# power.net
KiCad netlist of a schematic drawn in Altium Designer
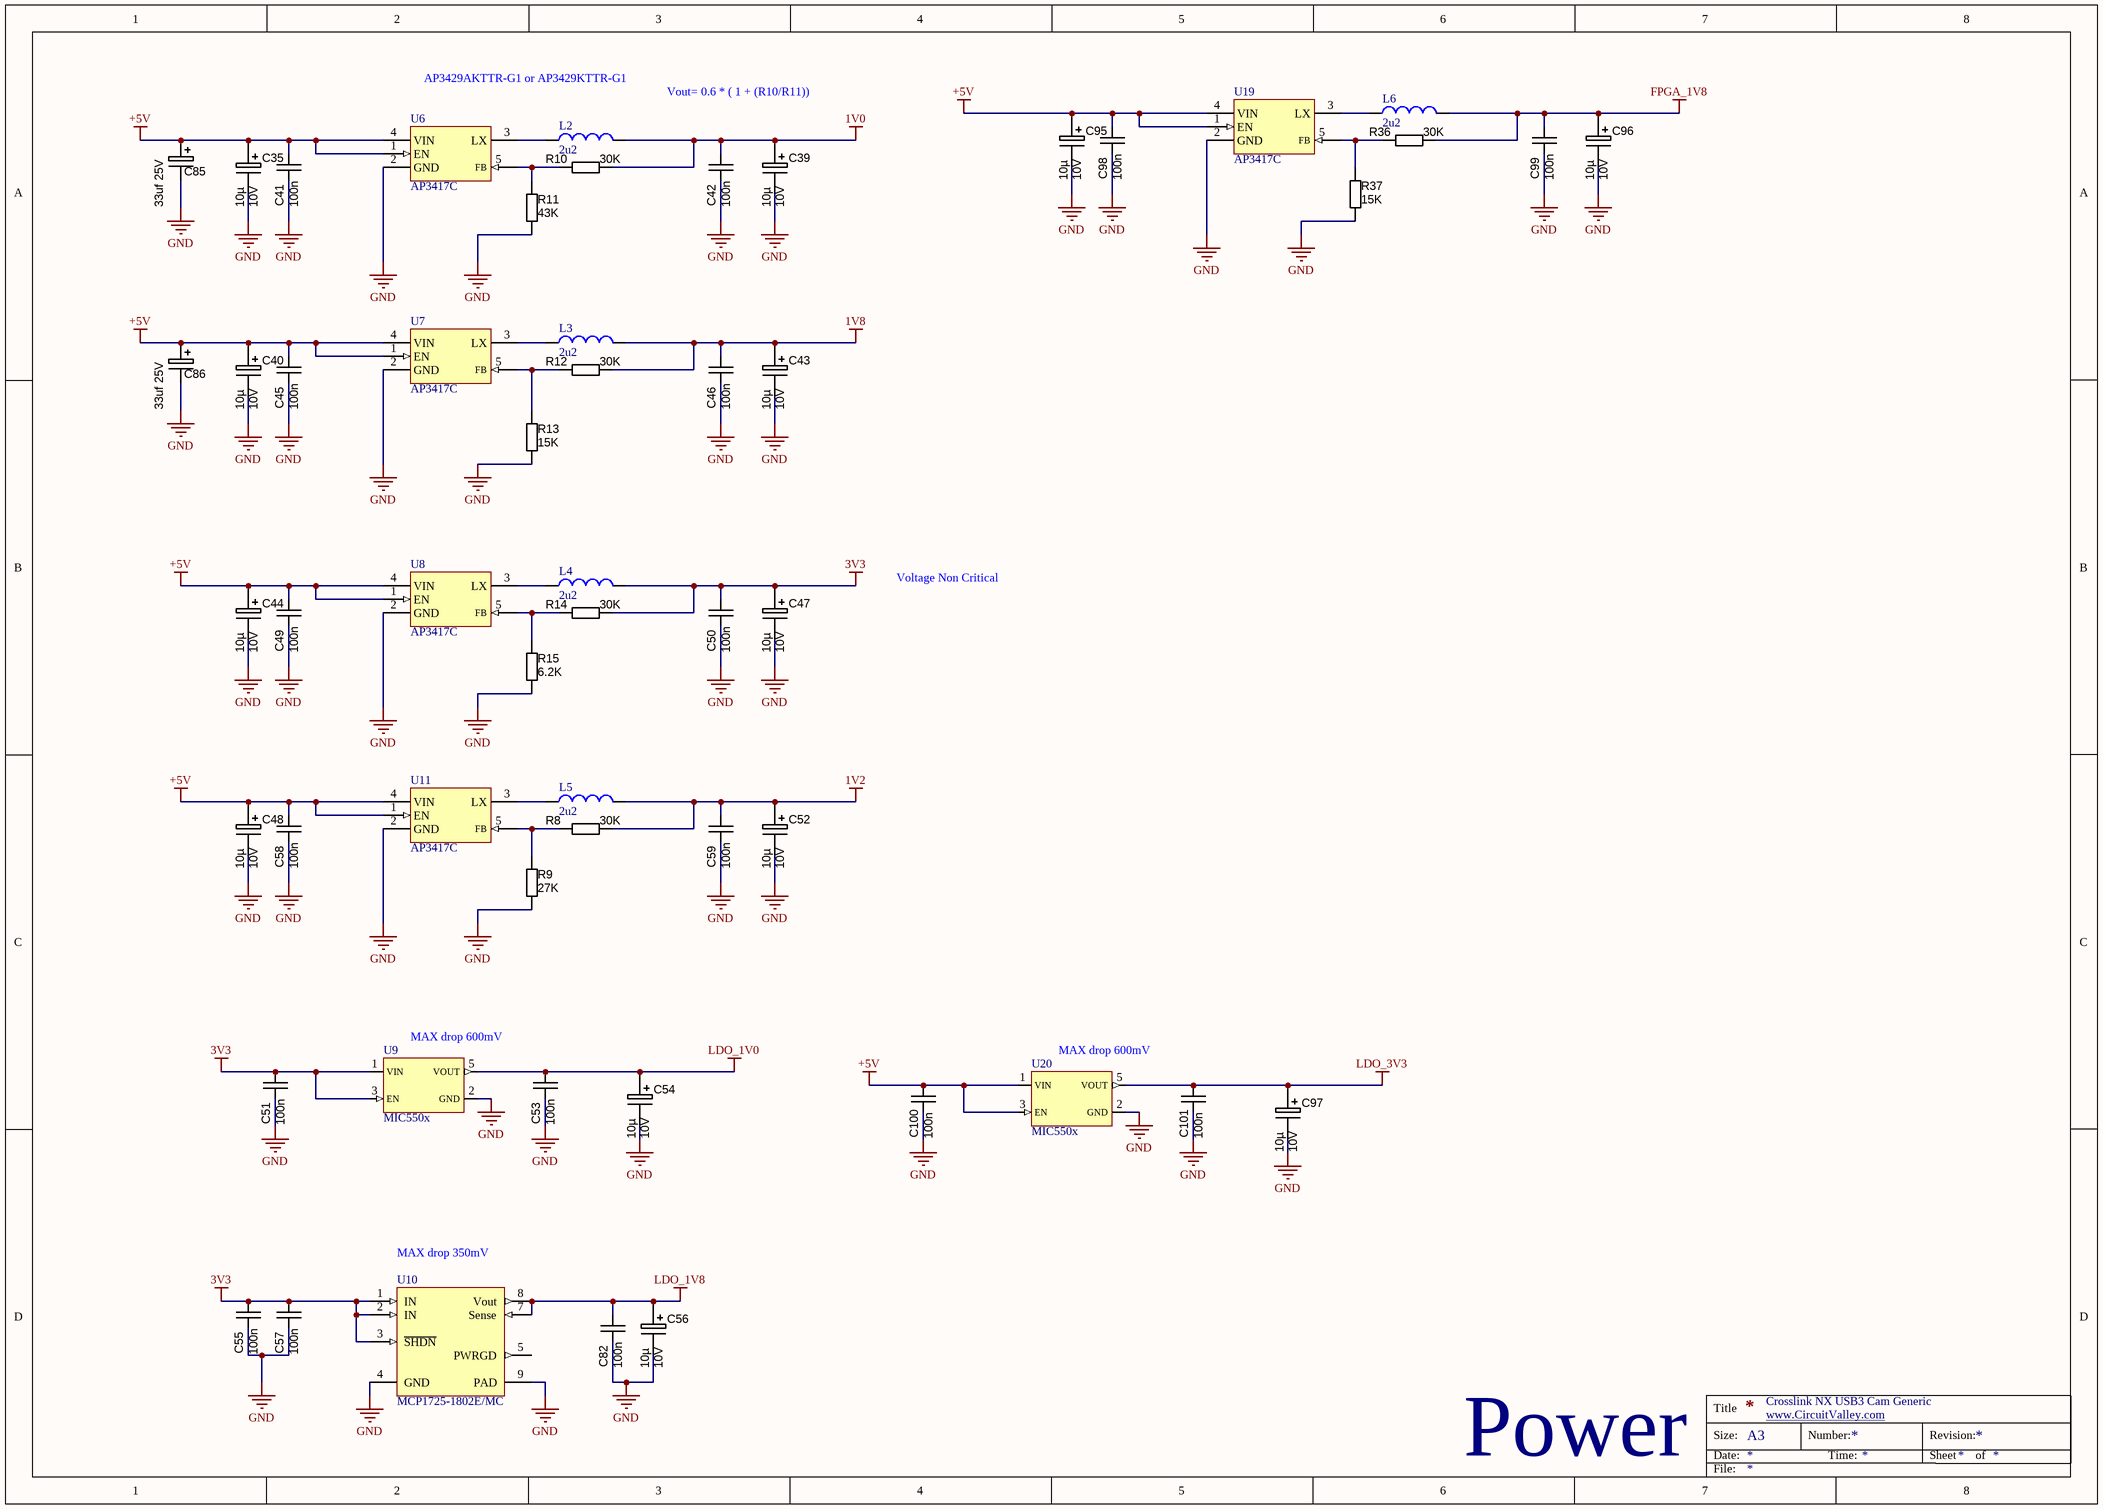
[diagram p0: power.SchDoc]

(export (version "E")
  (design (tool "Eeschema 10.0.6"))
  (components
    (comp (ref "C35")
      (value "10µ")
      (footprint "CAPMP3528X210N")
      (description "Capacitor SMD Tantalum 47uF 20% 6.3V 1210")
      (fields (field (name "TOLERANCE") "±20%") (field (name "RATINGS") "10V"))
      (libsource (lib "PBL - Capacitors") (part "CAPT_47u_1210_6V3"))
    )
    (comp (ref "C39")
      (value "10µ")
      (footprint "CAPMP3528X210N")
      (description "Capacitor SMD Tantalum 47uF 20% 6.3V 1210")
      (fields (field (name "TOLERANCE") "±20%") (field (name "RATINGS") "10V"))
      (libsource (lib "PBL - Capacitors") (part "CAPT_47u_1210_6V3"))
    )
    (comp (ref "C40")
      (value "10µ")
      (footprint "CAPMP3528X210N")
      (description "Capacitor SMD Tantalum 47uF 20% 6.3V 1210")
      (fields (field (name "TOLERANCE") "±20%") (field (name "RATINGS") "10V"))
      (libsource (lib "PBL - Capacitors") (part "CAPT_47u_1210_6V3"))
    )
    (comp (ref "C41")
      (value "100n")
      (footprint "CAPC1608N")
      (description "Capacitor SMD Cer 10pF 5% 50V NP0 0603")
      (fields (field (name "TOLERANCE") "±5%") (field (name "PART") "C0603X104K5RAC"))
      (libsource (lib "PBL - Capacitors") (part "CAPC_10p_0603_NP0_1%_50V"))
    )
    (comp (ref "C42")
      (value "100n")
      (footprint "CAPC1608N")
      (description "Capacitor SMD Cer 10pF 5% 50V NP0 0603")
      (fields (field (name "TOLERANCE") "±5%") (field (name "PART") "C0603X104K5RAC"))
      (libsource (lib "PBL - Capacitors") (part "CAPC_10p_0603_NP0_1%_50V"))
    )
    (comp (ref "C43")
      (value "10µ")
      (footprint "CAPMP3528X210N")
      (description "Capacitor SMD Tantalum 47uF 20% 6.3V 1210")
      (fields (field (name "TOLERANCE") "±20%") (field (name "RATINGS") "10V"))
      (libsource (lib "PBL - Capacitors") (part "CAPT_47u_1210_6V3"))
    )
    (comp (ref "C44")
      (value "10µ")
      (footprint "CAPMP3528X210N")
      (description "Capacitor SMD Tantalum 47uF 20% 6.3V 1210")
      (fields (field (name "TOLERANCE") "±20%") (field (name "RATINGS") "10V"))
      (libsource (lib "PBL - Capacitors") (part "CAPT_47u_1210_6V3"))
    )
    (comp (ref "C45")
      (value "100n")
      (footprint "CAPC1608N")
      (description "Capacitor SMD Cer 10pF 5% 50V NP0 0603")
      (fields (field (name "TOLERANCE") "±5%") (field (name "PART") "C0603X104K5RAC"))
      (libsource (lib "PBL - Capacitors") (part "CAPC_10p_0603_NP0_1%_50V"))
    )
    (comp (ref "C46")
      (value "100n")
      (footprint "CAPC1608N")
      (description "Capacitor SMD Cer 10pF 5% 50V NP0 0603")
      (fields (field (name "TOLERANCE") "±5%") (field (name "PART") "C0603X104K5RAC"))
      (libsource (lib "PBL - Capacitors") (part "CAPC_10p_0603_NP0_1%_50V"))
    )
    (comp (ref "C47")
      (value "10µ")
      (footprint "CAPMP3528X210N")
      (description "Capacitor SMD Tantalum 47uF 20% 6.3V 1210")
      (fields (field (name "TOLERANCE") "±20%") (field (name "RATINGS") "10V"))
      (libsource (lib "PBL - Capacitors") (part "CAPT_47u_1210_6V3"))
    )
    (comp (ref "C48")
      (value "10µ")
      (footprint "CAPMP3528X210N")
      (description "Capacitor SMD Tantalum 47uF 20% 6.3V 1210")
      (fields (field (name "TOLERANCE") "±20%") (field (name "RATINGS") "10V"))
      (libsource (lib "PBL - Capacitors") (part "CAPT_47u_1210_6V3"))
    )
    (comp (ref "C49")
      (value "100n")
      (footprint "CAPC1608N")
      (description "Capacitor SMD Cer 10pF 5% 50V NP0 0603")
      (fields (field (name "TOLERANCE") "±5%") (field (name "PART") "C0603X104K5RAC"))
      (libsource (lib "PBL - Capacitors") (part "CAPC_10p_0603_NP0_1%_50V"))
    )
    (comp (ref "C50")
      (value "100n")
      (footprint "CAPC1608N")
      (description "Capacitor SMD Cer 10pF 5% 50V NP0 0603")
      (fields (field (name "TOLERANCE") "±5%") (field (name "PART") "C0603X104K5RAC"))
      (libsource (lib "PBL - Capacitors") (part "CAPC_10p_0603_NP0_1%_50V"))
    )
    (comp (ref "C51")
      (value "100n")
      (footprint "CAPC1608N")
      (description "Capacitor SMD Cer 10pF 5% 50V NP0 0603")
      (fields (field (name "TOLERANCE") "±5%") (field (name "PART") "C0603X104K5RAC"))
      (libsource (lib "PBL - Capacitors") (part "CAPC_10p_0603_NP0_1%_50V"))
    )
    (comp (ref "C52")
      (value "10µ")
      (footprint "CAPMP3528X210N")
      (description "Capacitor SMD Tantalum 47uF 20% 6.3V 1210")
      (fields (field (name "TOLERANCE") "±20%") (field (name "RATINGS") "10V"))
      (libsource (lib "PBL - Capacitors") (part "CAPT_47u_1210_6V3"))
    )
    (comp (ref "C53")
      (value "100n")
      (footprint "CAPC1608N")
      (description "Capacitor SMD Cer 10pF 5% 50V NP0 0603")
      (fields (field (name "TOLERANCE") "±5%") (field (name "PART") "C0603X104K5RAC"))
      (libsource (lib "PBL - Capacitors") (part "CAPC_10p_0603_NP0_1%_50V"))
    )
    (comp (ref "C54")
      (value "10µ")
      (footprint "CAPMP3528X210N")
      (description "Capacitor SMD Tantalum 47uF 20% 6.3V 1210")
      (fields (field (name "TOLERANCE") "±20%") (field (name "RATINGS") "10V"))
      (libsource (lib "PBL - Capacitors") (part "CAPT_47u_1210_6V3"))
    )
    (comp (ref "C55")
      (value "100n")
      (footprint "CAPC1608N")
      (description "Capacitor SMD Cer 10pF 5% 50V NP0 0603")
      (fields (field (name "TOLERANCE") "±5%") (field (name "PART") "C0603X104K5RAC"))
      (libsource (lib "PBL - Capacitors") (part "CAPC_10p_0603_NP0_1%_50V"))
    )
    (comp (ref "C56")
      (value "10µ")
      (footprint "CAPMP3528X210N")
      (description "Capacitor SMD Tantalum 47uF 20% 6.3V 1210")
      (fields (field (name "TOLERANCE") "±20%") (field (name "RATINGS") "10V"))
      (libsource (lib "PBL - Capacitors") (part "CAPT_47u_1210_6V3"))
    )
    (comp (ref "C57")
      (value "100n")
      (footprint "CAPC1608N")
      (description "Capacitor SMD Cer 10pF 5% 50V NP0 0603")
      (fields (field (name "TOLERANCE") "±5%") (field (name "PART") "C0603X104K5RAC"))
      (libsource (lib "PBL - Capacitors") (part "CAPC_10p_0603_NP0_1%_50V"))
    )
    (comp (ref "C58")
      (value "100n")
      (footprint "CAPC1608N")
      (description "Capacitor SMD Cer 10pF 5% 50V NP0 0603")
      (fields (field (name "TOLERANCE") "±5%") (field (name "PART") "C0603X104K5RAC"))
      (libsource (lib "PBL - Capacitors") (part "CAPC_10p_0603_NP0_1%_50V"))
    )
    (comp (ref "C59")
      (value "100n")
      (footprint "CAPC1608N")
      (description "Capacitor SMD Cer 10pF 5% 50V NP0 0603")
      (fields (field (name "TOLERANCE") "±5%") (field (name "PART") "C0603X104K5RAC"))
      (libsource (lib "PBL - Capacitors") (part "CAPC_10p_0603_NP0_1%_50V"))
    )
    (comp (ref "C82")
      (value "100n")
      (footprint "CAPC1608N")
      (description "Capacitor SMD Cer 10pF 5% 50V NP0 0603")
      (fields (field (name "TOLERANCE") "±5%") (field (name "PART") "C0603X104K5RAC"))
      (libsource (lib "PBL - Capacitors") (part "CAPC_10p_0603_NP0_1%_50V"))
    )
    (comp (ref "C85")
      (value "33uf 25V")
      (footprint "CAPMP7343X310N")
      (description "Capacitor SMD Tant 330uF 20% 6V3 2917")
      (fields
        (field (name "TOLERANCE") "±20%")
        (field (name "MANUFACTURER PART NUMBER") "T520D337M006ATE015")
      )
      (libsource (lib "PBL - Capacitors") (part "CAPT_330u_2917_6V3"))
    )
    (comp (ref "C86")
      (value "33uf 25V")
      (footprint "CAPMP7343X310N")
      (description "Capacitor SMD Tant 330uF 20% 6V3 2917")
      (fields
        (field (name "TOLERANCE") "±20%")
        (field (name "MANUFACTURER PART NUMBER") "T520D337M006ATE015")
      )
      (libsource (lib "PBL - Capacitors") (part "CAPT_330u_2917_6V3"))
    )
    (comp (ref "C95")
      (value "10µ")
      (footprint "CAPMP3528X210N")
      (description "Capacitor SMD Tantalum 47uF 20% 6.3V 1210")
      (fields (field (name "TOLERANCE") "±20%") (field (name "RATINGS") "10V"))
      (libsource (lib "PBL - Capacitors") (part "CAPT_47u_1210_6V3"))
    )
    (comp (ref "C96")
      (value "10µ")
      (footprint "CAPMP3528X210N")
      (description "Capacitor SMD Tantalum 47uF 20% 6.3V 1210")
      (fields (field (name "TOLERANCE") "±20%") (field (name "RATINGS") "10V"))
      (libsource (lib "PBL - Capacitors") (part "CAPT_47u_1210_6V3"))
    )
    (comp (ref "C97")
      (value "10µ")
      (footprint "CAPMP3528X210N")
      (description "Capacitor SMD Tantalum 47uF 20% 6.3V 1210")
      (fields (field (name "TOLERANCE") "±20%") (field (name "RATINGS") "10V"))
      (libsource (lib "PBL - Capacitors") (part "CAPT_47u_1210_6V3"))
    )
    (comp (ref "C98")
      (value "100n")
      (footprint "CAPC1608N")
      (description "Capacitor SMD Cer 10pF 5% 50V NP0 0603")
      (fields (field (name "TOLERANCE") "±5%") (field (name "PART") "C0603X104K5RAC"))
      (libsource (lib "PBL - Capacitors") (part "CAPC_10p_0603_NP0_1%_50V"))
    )
    (comp (ref "C99")
      (value "100n")
      (footprint "CAPC1608N")
      (description "Capacitor SMD Cer 10pF 5% 50V NP0 0603")
      (fields (field (name "TOLERANCE") "±5%") (field (name "PART") "C0603X104K5RAC"))
      (libsource (lib "PBL - Capacitors") (part "CAPC_10p_0603_NP0_1%_50V"))
    )
    (comp (ref "C100")
      (value "100n")
      (footprint "CAPC1608N")
      (description "Capacitor SMD Cer 10pF 5% 50V NP0 0603")
      (fields (field (name "TOLERANCE") "±5%") (field (name "PART") "C0603X104K5RAC"))
      (libsource (lib "PBL - Capacitors") (part "CAPC_10p_0603_NP0_1%_50V"))
    )
    (comp (ref "C101")
      (value "100n")
      (footprint "CAPC1608N")
      (description "Capacitor SMD Cer 10pF 5% 50V NP0 0603")
      (fields (field (name "TOLERANCE") "±5%") (field (name "PART") "C0603X104K5RAC"))
      (libsource (lib "PBL - Capacitors") (part "CAPC_10p_0603_NP0_1%_50V"))
    )
    (comp (ref "L2")
      (value "2u2")
      (footprint "TAIYO_NRS4018T2R2MDGJ")
      (fields (field (name "PARTNUMBER") "NRS4018T2R2MDGJ"))
      (libsource (lib "Inductor") (part "inductor_smd"))
    )
    (comp (ref "L3")
      (value "2u2")
      (footprint "TAIYO_NRS4018T2R2MDGJ")
      (fields (field (name "PARTNUMBER") "NRS4018T2R2MDGJ"))
      (libsource (lib "Inductor") (part "inductor_smd"))
    )
    (comp (ref "L4")
      (value "2u2")
      (footprint "TAIYO_NRS4018T2R2MDGJ")
      (fields (field (name "PARTNUMBER") "NRS4018T2R2MDGJ"))
      (libsource (lib "Inductor") (part "inductor_smd"))
    )
    (comp (ref "L5")
      (value "2u2")
      (footprint "TAIYO_NRS4018T2R2MDGJ")
      (fields (field (name "PARTNUMBER") "NRS4018T2R2MDGJ"))
      (libsource (lib "Inductor") (part "inductor_smd"))
    )
    (comp (ref "L6")
      (value "2u2")
      (footprint "TAIYO_NRS4018T2R2MDGJ")
      (fields (field (name "PARTNUMBER") "NRS4018T2R2MDGJ"))
      (libsource (lib "Inductor") (part "inductor_smd"))
    )
    (comp (ref "R8")
      (value "30K")
      (footprint "RESC1608N_ZERO")
      (description "Resistor SMD chip 0.0 Ohm 0.1W 0603")
      (fields (field (name "TOLERANCE") "±5%") (field (name "Comment") "Thick Film"))
      (libsource (lib "PBL - Resistors") (part "RES_0R_0603"))
    )
    (comp (ref "R9")
      (value "27K")
      (footprint "RESC1608N_ZERO")
      (description "Resistor SMD chip 0.0 Ohm 0.1W 0603")
      (fields (field (name "TOLERANCE") "±5%") (field (name "Comment") "Thick Film"))
      (libsource (lib "") (part "RES_0R_0603_1"))
    )
    (comp (ref "R10")
      (value "30K")
      (footprint "RESC1608N_ZERO")
      (description "Resistor SMD chip 0.0 Ohm 0.1W 0603")
      (fields (field (name "TOLERANCE") "±5%") (field (name "Comment") "Thick Film"))
      (libsource (lib "PBL - Resistors") (part "RES_0R_0603"))
    )
    (comp (ref "R11")
      (value "43K")
      (footprint "RESC1608N_ZERO")
      (description "Resistor SMD chip 0.0 Ohm 0.1W 0603")
      (fields (field (name "TOLERANCE") "±5%") (field (name "Comment") "Thick Film"))
      (libsource (lib "") (part "RES_0R_0603_1"))
    )
    (comp (ref "R12")
      (value "30K")
      (footprint "RESC1608N_ZERO")
      (description "Resistor SMD chip 0.0 Ohm 0.1W 0603")
      (fields (field (name "TOLERANCE") "±5%") (field (name "Comment") "Thick Film"))
      (libsource (lib "PBL - Resistors") (part "RES_0R_0603"))
    )
    (comp (ref "R13")
      (value "15K")
      (footprint "RESC1608N_ZERO")
      (description "Resistor SMD chip 0.0 Ohm 0.1W 0603")
      (fields (field (name "TOLERANCE") "±5%") (field (name "Comment") "Thick Film"))
      (libsource (lib "") (part "RES_0R_0603_1"))
    )
    (comp (ref "R14")
      (value "30K")
      (footprint "RESC1608N_ZERO")
      (description "Resistor SMD chip 0.0 Ohm 0.1W 0603")
      (fields (field (name "TOLERANCE") "±5%") (field (name "Comment") "Thick Film"))
      (libsource (lib "PBL - Resistors") (part "RES_0R_0603"))
    )
    (comp (ref "R15")
      (value "6.2K")
      (footprint "RESC1608N_ZERO")
      (description "Resistor SMD chip 0.0 Ohm 0.1W 0603")
      (fields (field (name "TOLERANCE") "±5%") (field (name "Comment") "Thick Film"))
      (libsource (lib "") (part "RES_0R_0603_1"))
    )
    (comp (ref "R36")
      (value "30K")
      (footprint "RESC1608N_ZERO")
      (description "Resistor SMD chip 0.0 Ohm 0.1W 0603")
      (fields (field (name "TOLERANCE") "±5%") (field (name "Comment") "Thick Film"))
      (libsource (lib "PBL - Resistors") (part "RES_0R_0603"))
    )
    (comp (ref "R37")
      (value "15K")
      (footprint "RESC1608N_ZERO")
      (description "Resistor SMD chip 0.0 Ohm 0.1W 0603")
      (fields (field (name "TOLERANCE") "±5%") (field (name "Comment") "Thick Film"))
      (libsource (lib "") (part "RES_0R_0603_1"))
    )
    (comp (ref "U6") (value "AP3417C") (footprint "SOT23-5") (libsource (lib "cvlib") (part "AP3417C")))
    (comp (ref "U7") (value "AP3417C") (footprint "SOT23-5") (libsource (lib "cvlib") (part "AP3417C")))
    (comp (ref "U8") (value "AP3417C") (footprint "SOT23-5") (libsource (lib "cvlib") (part "AP3417C")))
    (comp (ref "U9") (value "MIC550x") (footprint "SOT23-5") (libsource (lib "cvlib") (part "MIC550x")))
    (comp (ref "U10")
      (value "MCP1725-1802E/MC")
      (footprint "DFN8_3x2")
      (description "LDO")
      (libsource (lib "cvlib") (part "MCP1725"))
    )
    (comp (ref "U11") (value "AP3417C") (footprint "SOT23-5") (libsource (lib "cvlib") (part "AP3417C")))
    (comp (ref "U19") (value "AP3417C") (footprint "SOT23-5") (libsource (lib "cvlib") (part "AP3417C")))
    (comp (ref "U20") (value "MIC550x") (footprint "SOT23-5") (libsource (lib "cvlib") (part "MIC550x")))
  )
  (nets
    (net (code "1") (name "+5V") (class "Default")
      (node (ref "C100") (pin "2") (pintype "passive"))
      (node (ref "C35") (pin "1") (pintype "passive"))
      (node (ref "C40") (pin "1") (pintype "passive"))
      (node (ref "C41") (pin "2") (pintype "passive"))
      (node (ref "C44") (pin "1") (pintype "passive"))
      (node (ref "C45") (pin "2") (pintype "passive"))
      (node (ref "C48") (pin "1") (pintype "passive"))
      (node (ref "C49") (pin "2") (pintype "passive"))
      (node (ref "C58") (pin "2") (pintype "passive"))
      (node (ref "C85") (pin "1") (pintype "passive"))
      (node (ref "C86") (pin "1") (pintype "passive"))
      (node (ref "C95") (pin "1") (pintype "passive"))
      (node (ref "C98") (pin "2") (pintype "passive"))
      (node (ref "U11") (pin "1") (pinfunction "EN_1") (pintype "input"))
      (node (ref "U11") (pin "4") (pinfunction "VIN_4") (pintype "power_in"))
      (node (ref "U19") (pin "1") (pinfunction "EN_1") (pintype "input"))
      (node (ref "U19") (pin "4") (pinfunction "VIN_4") (pintype "power_in"))
      (node (ref "U20") (pin "1") (pinfunction "VIN_1") (pintype "power_in"))
      (node (ref "U20") (pin "3") (pinfunction "EN_3") (pintype "input"))
      (node (ref "U6") (pin "1") (pinfunction "EN_1") (pintype "input"))
      (node (ref "U6") (pin "4") (pinfunction "VIN_4") (pintype "power_in"))
      (node (ref "U7") (pin "1") (pinfunction "EN_1") (pintype "input"))
      (node (ref "U7") (pin "4") (pinfunction "VIN_4") (pintype "power_in"))
      (node (ref "U8") (pin "1") (pinfunction "EN_1") (pintype "input"))
      (node (ref "U8") (pin "4") (pinfunction "VIN_4") (pintype "power_in"))
    )
    (net (code "2") (name "1V0") (class "Default")
      (node (ref "C39") (pin "1") (pintype "passive"))
      (node (ref "C42") (pin "2") (pintype "passive"))
      (node (ref "L2") (pin "2") (pinfunction "2_2") (pintype "passive"))
      (node (ref "R10") (pin "1") (pinfunction "1_1") (pintype "passive"))
    )
    (net (code "3") (name "1V2") (class "Default")
      (node (ref "C52") (pin "1") (pintype "passive"))
      (node (ref "C59") (pin "2") (pintype "passive"))
      (node (ref "L5") (pin "2") (pinfunction "2_2") (pintype "passive"))
      (node (ref "R8") (pin "1") (pinfunction "1_1") (pintype "passive"))
    )
    (net (code "4") (name "1V8") (class "Default")
      (node (ref "C43") (pin "1") (pintype "passive"))
      (node (ref "C46") (pin "2") (pintype "passive"))
      (node (ref "L3") (pin "2") (pinfunction "2_2") (pintype "passive"))
      (node (ref "R12") (pin "1") (pinfunction "1_1") (pintype "passive"))
    )
    (net (code "5") (name "3V3") (class "Default")
      (node (ref "C47") (pin "1") (pintype "passive"))
      (node (ref "C50") (pin "2") (pintype "passive"))
      (node (ref "C51") (pin "2") (pintype "passive"))
      (node (ref "C55") (pin "2") (pintype "passive"))
      (node (ref "C57") (pin "2") (pintype "passive"))
      (node (ref "L4") (pin "2") (pinfunction "2_2") (pintype "passive"))
      (node (ref "R14") (pin "1") (pinfunction "1_1") (pintype "passive"))
      (node (ref "U10") (pin "1") (pinfunction "IN_1") (pintype "input"))
      (node (ref "U10") (pin "2") (pinfunction "IN_2") (pintype "input"))
      (node (ref "U10") (pin "3") (pinfunction "~{SHDN}_3") (pintype "input"))
      (node (ref "U9") (pin "1") (pinfunction "VIN_1") (pintype "power_in"))
      (node (ref "U9") (pin "3") (pinfunction "EN_3") (pintype "input"))
    )
    (net (code "6") (name "FPGA_1V8") (class "Default")
      (node (ref "C96") (pin "1") (pintype "passive"))
      (node (ref "C99") (pin "2") (pintype "passive"))
      (node (ref "L6") (pin "2") (pinfunction "2_2") (pintype "passive"))
      (node (ref "R36") (pin "1") (pinfunction "1_1") (pintype "passive"))
    )
    (net (code "7") (name "GND") (class "Default")
      (node (ref "C100") (pin "1") (pintype "passive"))
      (node (ref "C101") (pin "1") (pintype "passive"))
      (node (ref "C35") (pin "2") (pintype "passive"))
      (node (ref "C39") (pin "2") (pintype "passive"))
      (node (ref "C40") (pin "2") (pintype "passive"))
      (node (ref "C41") (pin "1") (pintype "passive"))
      (node (ref "C42") (pin "1") (pintype "passive"))
      (node (ref "C43") (pin "2") (pintype "passive"))
      (node (ref "C44") (pin "2") (pintype "passive"))
      (node (ref "C45") (pin "1") (pintype "passive"))
      (node (ref "C46") (pin "1") (pintype "passive"))
      (node (ref "C47") (pin "2") (pintype "passive"))
      (node (ref "C48") (pin "2") (pintype "passive"))
      (node (ref "C49") (pin "1") (pintype "passive"))
      (node (ref "C50") (pin "1") (pintype "passive"))
      (node (ref "C51") (pin "1") (pintype "passive"))
      (node (ref "C52") (pin "2") (pintype "passive"))
      (node (ref "C53") (pin "1") (pintype "passive"))
      (node (ref "C54") (pin "2") (pintype "passive"))
      (node (ref "C55") (pin "1") (pintype "passive"))
      (node (ref "C56") (pin "2") (pintype "passive"))
      (node (ref "C57") (pin "1") (pintype "passive"))
      (node (ref "C58") (pin "1") (pintype "passive"))
      (node (ref "C59") (pin "1") (pintype "passive"))
      (node (ref "C82") (pin "1") (pintype "passive"))
      (node (ref "C85") (pin "2") (pintype "passive"))
      (node (ref "C86") (pin "2") (pintype "passive"))
      (node (ref "C95") (pin "2") (pintype "passive"))
      (node (ref "C96") (pin "2") (pintype "passive"))
      (node (ref "C97") (pin "2") (pintype "passive"))
      (node (ref "C98") (pin "1") (pintype "passive"))
      (node (ref "C99") (pin "1") (pintype "passive"))
      (node (ref "R11") (pin "2") (pinfunction "2_2") (pintype "passive"))
      (node (ref "R13") (pin "2") (pinfunction "2_2") (pintype "passive"))
      (node (ref "R15") (pin "2") (pinfunction "2_2") (pintype "passive"))
      (node (ref "R37") (pin "2") (pinfunction "2_2") (pintype "passive"))
      (node (ref "R9") (pin "2") (pinfunction "2_2") (pintype "passive"))
      (node (ref "U10") (pin "4") (pinfunction "GND_4") (pintype "passive"))
      (node (ref "U10") (pin "9") (pinfunction "PAD_9") (pintype "passive"))
      (node (ref "U11") (pin "2") (pinfunction "GND_2") (pintype "power_in"))
      (node (ref "U19") (pin "2") (pinfunction "GND_2") (pintype "power_in"))
      (node (ref "U20") (pin "2") (pinfunction "GND_2") (pintype "power_in"))
      (node (ref "U6") (pin "2") (pinfunction "GND_2") (pintype "power_in"))
      (node (ref "U7") (pin "2") (pinfunction "GND_2") (pintype "power_in"))
      (node (ref "U8") (pin "2") (pinfunction "GND_2") (pintype "power_in"))
      (node (ref "U9") (pin "2") (pinfunction "GND_2") (pintype "power_in"))
    )
    (net (code "8") (name "LDO_1V0") (class "Default")
      (node (ref "C53") (pin "2") (pintype "passive"))
      (node (ref "C54") (pin "1") (pintype "passive"))
      (node (ref "U9") (pin "5") (pinfunction "VOUT_5") (pintype "output"))
    )
    (net (code "9") (name "LDO_1V8") (class "Default")
      (node (ref "C56") (pin "1") (pintype "passive"))
      (node (ref "C82") (pin "2") (pintype "passive"))
      (node (ref "U10") (pin "7") (pinfunction "Sense_7") (pintype "input"))
      (node (ref "U10") (pin "8") (pinfunction "Vout_8") (pintype "output"))
    )
    (net (code "10") (name "LDO_3V3") (class "Default")
      (node (ref "C101") (pin "2") (pintype "passive"))
      (node (ref "C97") (pin "1") (pintype "passive"))
      (node (ref "U20") (pin "5") (pinfunction "VOUT_5") (pintype "output"))
    )
    (net (code "11") (name "Net-(U6-FB)") (class "Default")
      (node (ref "R10") (pin "2") (pinfunction "2_2") (pintype "passive"))
      (node (ref "R11") (pin "1") (pinfunction "1_1") (pintype "passive"))
      (node (ref "U6") (pin "5") (pinfunction "FB_5") (pintype "input"))
    )
    (net (code "12") (name "Net-(U6-LX)") (class "Default")
      (node (ref "L2") (pin "1") (pinfunction "1_1") (pintype "passive"))
      (node (ref "U6") (pin "3") (pinfunction "LX_3") (pintype "passive"))
    )
    (net (code "13") (name "Net-(U7-FB)") (class "Default")
      (node (ref "R12") (pin "2") (pinfunction "2_2") (pintype "passive"))
      (node (ref "R13") (pin "1") (pinfunction "1_1") (pintype "passive"))
      (node (ref "U7") (pin "5") (pinfunction "FB_5") (pintype "input"))
    )
    (net (code "14") (name "Net-(U7-LX)") (class "Default")
      (node (ref "L3") (pin "1") (pinfunction "1_1") (pintype "passive"))
      (node (ref "U7") (pin "3") (pinfunction "LX_3") (pintype "passive"))
    )
    (net (code "15") (name "Net-(U8-FB)") (class "Default")
      (node (ref "R14") (pin "2") (pinfunction "2_2") (pintype "passive"))
      (node (ref "R15") (pin "1") (pinfunction "1_1") (pintype "passive"))
      (node (ref "U8") (pin "5") (pinfunction "FB_5") (pintype "input"))
    )
    (net (code "16") (name "Net-(U8-LX)") (class "Default")
      (node (ref "L4") (pin "1") (pinfunction "1_1") (pintype "passive"))
      (node (ref "U8") (pin "3") (pinfunction "LX_3") (pintype "passive"))
    )
    (net (code "17") (name "Net-(U11-FB)") (class "Default")
      (node (ref "R8") (pin "2") (pinfunction "2_2") (pintype "passive"))
      (node (ref "R9") (pin "1") (pinfunction "1_1") (pintype "passive"))
      (node (ref "U11") (pin "5") (pinfunction "FB_5") (pintype "input"))
    )
    (net (code "18") (name "Net-(U11-LX)") (class "Default")
      (node (ref "L5") (pin "1") (pinfunction "1_1") (pintype "passive"))
      (node (ref "U11") (pin "3") (pinfunction "LX_3") (pintype "passive"))
    )
    (net (code "19") (name "Net-(U19-FB)") (class "Default")
      (node (ref "R36") (pin "2") (pinfunction "2_2") (pintype "passive"))
      (node (ref "R37") (pin "1") (pinfunction "1_1") (pintype "passive"))
      (node (ref "U19") (pin "5") (pinfunction "FB_5") (pintype "input"))
    )
    (net (code "20") (name "Net-(U19-LX)") (class "Default")
      (node (ref "L6") (pin "1") (pinfunction "1_1") (pintype "passive"))
      (node (ref "U19") (pin "3") (pinfunction "LX_3") (pintype "passive"))
    )
    (net (code "21") (name "unconnected-(U10-PWRGD-Pad5)") (class "Default")
      (node (ref "U10") (pin "5") (pinfunction "PWRGD_5") (pintype "output"))
    )
  )
)
